# Board.net
KiCad netlist of a schematic drawn in EAGLE
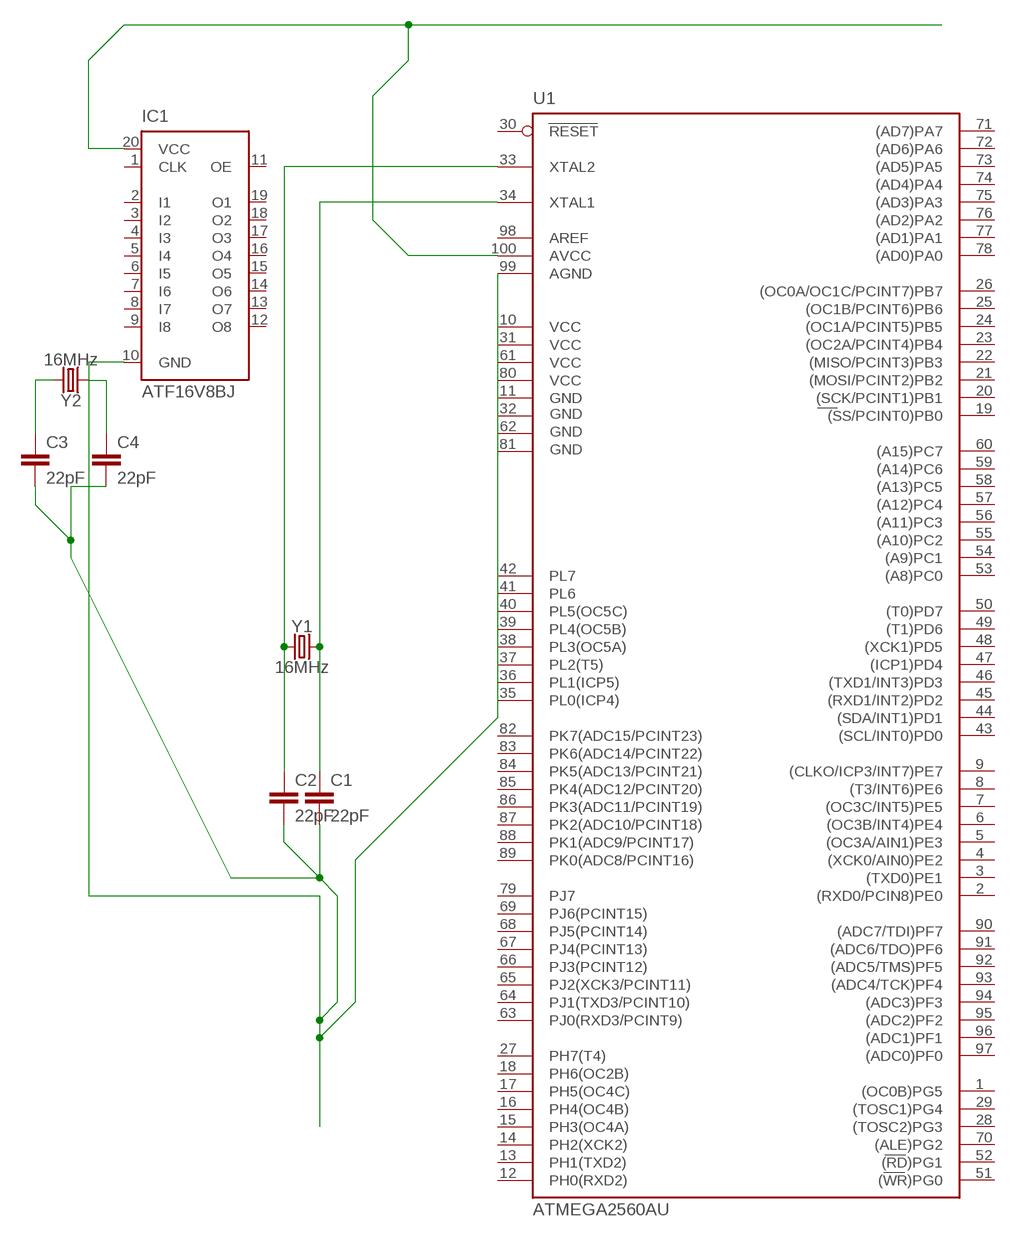
[diagram p0: schematic, sheet 1]

(export (version "E")
  (design (tool "Eeschema 10.0.6"))
  (components
    (comp (ref "C1")
      (value "22pF")
      (footprint "eagle-import:0603")
      (libsource (lib "eagle-import") (part "22PF-0603-50V-5%"))
    )
    (comp (ref "C2")
      (value "22pF")
      (footprint "eagle-import:0603")
      (libsource (lib "eagle-import") (part "22PF-0603-50V-5%"))
    )
    (comp (ref "C3")
      (value "22pF")
      (footprint "eagle-import:0603")
      (libsource (lib "eagle-import") (part "22PF-0603-50V-5%"))
    )
    (comp (ref "C4")
      (value "22pF")
      (footprint "eagle-import:0603")
      (libsource (lib "eagle-import") (part "22PF-0603-50V-5%"))
    )
    (comp (ref "IC1")
      (value "ATF16V8BJ")
      (footprint "eagle-import:PLCC20")
      (fields (field (name "MPN") "ATF16V8CZ-15JU"))
      (libsource (lib "eagle-import") (part "ATF16V8BJ"))
    )
    (comp (ref "U1")
      (value "ATMEGA2560AU")
      (footprint "eagle-import:TQFP100")
      (libsource (lib "eagle-import") (part "ATMEGA2560AU"))
    )
    (comp (ref "Y1")
      (value "16MHz")
      (footprint "eagle-import:CRYSTAL-SMD-5X3.2-4PAD")
      (libsource (lib "eagle-import") (part "CRYSTAL-16MHZSMD-5X3.2"))
    )
    (comp (ref "Y2")
      (value "16MHz")
      (footprint "eagle-import:CRYSTAL-SMD-5X3.2-4PAD")
      (libsource (lib "eagle-import") (part "CRYSTAL-16MHZSMD-5X3.2"))
    )
  )
  (nets
    (net (code "1") (name "/GND") (class "Default")
      (node (ref "U1") (pin "11") (pinfunction "GND_11") (pintype "power_in"))
    )
    (net (code "2") (name "/GND1") (class "Default")
      (node (ref "U1") (pin "32") (pinfunction "GND1_32") (pintype "power_in"))
    )
    (net (code "3") (name "/GND2") (class "Default")
      (node (ref "U1") (pin "62") (pinfunction "GND2_62") (pintype "power_in"))
    )
    (net (code "4") (name "/GND3") (class "Default")
      (node (ref "U1") (pin "81") (pinfunction "GND3_81") (pintype "power_in"))
    )
    (net (code "5") (name "/VCC") (class "Default")
      (node (ref "U1") (pin "10") (pinfunction "VCC_10") (pintype "power_in"))
    )
    (net (code "6") (name "/VCC1") (class "Default")
      (node (ref "U1") (pin "31") (pinfunction "VCC1_31") (pintype "power_in"))
    )
    (net (code "7") (name "/VCC2") (class "Default")
      (node (ref "U1") (pin "61") (pinfunction "VCC2_61") (pintype "power_in"))
    )
    (net (code "8") (name "/VCC3") (class "Default")
      (node (ref "U1") (pin "80") (pinfunction "VCC3_80") (pintype "power_in"))
    )
    (net (code "9") (name "Net-(C4-Pad1)") (class "Default")
      (node (ref "C4") (pin "1") (pinfunction "1_1") (pintype "passive"))
      (node (ref "Y2") (pin "1") (pinfunction "1_1") (pintype "passive"))
    )
    (net (code "10") (name "Net-(IC1-GND)") (class "Default")
      (node (ref "C1") (pin "2") (pinfunction "2_2") (pintype "passive"))
      (node (ref "C2") (pin "2") (pinfunction "2_2") (pintype "passive"))
      (node (ref "C3") (pin "2") (pinfunction "2_2") (pintype "passive"))
      (node (ref "C4") (pin "2") (pinfunction "2_2") (pintype "passive"))
      (node (ref "IC1") (pin "10") (pinfunction "GND_10") (pintype "power_in"))
      (node (ref "U1") (pin "99") (pinfunction "AGND_99") (pintype "power_in"))
    )
    (net (code "11") (name "Net-(IC1-VCC)") (class "Default")
      (node (ref "IC1") (pin "20") (pinfunction "VCC_20") (pintype "power_in"))
      (node (ref "U1") (pin "100") (pinfunction "AVCC_100") (pintype "power_in"))
    )
    (net (code "12") (name "Net-(U1-XTAL1)") (class "Default")
      (node (ref "C1") (pin "1") (pinfunction "1_1") (pintype "passive"))
      (node (ref "U1") (pin "34") (pinfunction "XTAL1_34") (pintype "input"))
      (node (ref "Y1") (pin "3") (pinfunction "2_3") (pintype "passive"))
    )
    (net (code "13") (name "Net-(U1-XTAL2)") (class "Default")
      (node (ref "C2") (pin "1") (pinfunction "1_1") (pintype "passive"))
      (node (ref "U1") (pin "33") (pinfunction "XTAL2_33") (pintype "output"))
      (node (ref "Y1") (pin "1") (pinfunction "1_1") (pintype "passive"))
    )
    (net (code "14") (name "Net-(Y2-2)") (class "Default")
      (node (ref "C3") (pin "1") (pinfunction "1_1") (pintype "passive"))
      (node (ref "Y2") (pin "3") (pinfunction "2_3") (pintype "passive"))
    )
    (net (code "15") (name "unconnected-(IC1-CLK-Pad1)") (class "Default")
      (node (ref "IC1") (pin "1") (pinfunction "CLK_1") (pintype "input"))
    )
    (net (code "16") (name "unconnected-(IC1-I1-Pad2)") (class "Default")
      (node (ref "IC1") (pin "2") (pinfunction "I1_2") (pintype "input"))
    )
    (net (code "17") (name "unconnected-(IC1-I2-Pad3)") (class "Default")
      (node (ref "IC1") (pin "3") (pinfunction "I2_3") (pintype "input"))
    )
    (net (code "18") (name "unconnected-(IC1-I3-Pad4)") (class "Default")
      (node (ref "IC1") (pin "4") (pinfunction "I3_4") (pintype "input"))
    )
    (net (code "19") (name "unconnected-(IC1-I4-Pad5)") (class "Default")
      (node (ref "IC1") (pin "5") (pinfunction "I4_5") (pintype "input"))
    )
    (net (code "20") (name "unconnected-(IC1-I5-Pad6)") (class "Default")
      (node (ref "IC1") (pin "6") (pinfunction "I5_6") (pintype "input"))
    )
    (net (code "21") (name "unconnected-(IC1-I6-Pad7)") (class "Default")
      (node (ref "IC1") (pin "7") (pinfunction "I6_7") (pintype "input"))
    )
    (net (code "22") (name "unconnected-(IC1-I7-Pad8)") (class "Default")
      (node (ref "IC1") (pin "8") (pinfunction "I7_8") (pintype "input"))
    )
    (net (code "23") (name "unconnected-(IC1-I8-Pad9)") (class "Default")
      (node (ref "IC1") (pin "9") (pinfunction "I8_9") (pintype "input"))
    )
    (net (code "24") (name "unconnected-(IC1-O1-Pad19)") (class "Default")
      (node (ref "IC1") (pin "19") (pinfunction "O1_19") (pintype "output"))
    )
    (net (code "25") (name "unconnected-(IC1-O2-Pad18)") (class "Default")
      (node (ref "IC1") (pin "18") (pinfunction "O2_18") (pintype "output"))
    )
    (net (code "26") (name "unconnected-(IC1-O3-Pad17)") (class "Default")
      (node (ref "IC1") (pin "17") (pinfunction "O3_17") (pintype "output"))
    )
    (net (code "27") (name "unconnected-(IC1-O4-Pad16)") (class "Default")
      (node (ref "IC1") (pin "16") (pinfunction "O4_16") (pintype "output"))
    )
    (net (code "28") (name "unconnected-(IC1-O5-Pad15)") (class "Default")
      (node (ref "IC1") (pin "15") (pinfunction "O5_15") (pintype "output"))
    )
    (net (code "29") (name "unconnected-(IC1-O6-Pad14)") (class "Default")
      (node (ref "IC1") (pin "14") (pinfunction "O6_14") (pintype "output"))
    )
    (net (code "30") (name "unconnected-(IC1-O7-Pad13)") (class "Default")
      (node (ref "IC1") (pin "13") (pinfunction "O7_13") (pintype "output"))
    )
    (net (code "31") (name "unconnected-(IC1-O8-Pad12)") (class "Default")
      (node (ref "IC1") (pin "12") (pinfunction "O8_12") (pintype "output"))
    )
    (net (code "32") (name "unconnected-(IC1-OE-Pad11)") (class "Default")
      (node (ref "IC1") (pin "11") (pinfunction "OE_11") (pintype "input"))
    )
    (net (code "33") (name "unconnected-(U1-(A8)PC0-Pad53)") (class "Default")
      (node (ref "U1") (pin "53") (pinfunction "(A8)PC0_53") (pintype "bidirectional"))
    )
    (net (code "34") (name "unconnected-(U1-(A9)PC1-Pad54)") (class "Default")
      (node (ref "U1") (pin "54") (pinfunction "(A9)PC1_54") (pintype "bidirectional"))
    )
    (net (code "35") (name "unconnected-(U1-(A10)PC2-Pad55)") (class "Default")
      (node (ref "U1") (pin "55") (pinfunction "(A10)PC2_55") (pintype "bidirectional"))
    )
    (net (code "36") (name "unconnected-(U1-(A11)PC3-Pad56)") (class "Default")
      (node (ref "U1") (pin "56") (pinfunction "(A11)PC3_56") (pintype "bidirectional"))
    )
    (net (code "37") (name "unconnected-(U1-(A12)PC4-Pad57)") (class "Default")
      (node (ref "U1") (pin "57") (pinfunction "(A12)PC4_57") (pintype "bidirectional"))
    )
    (net (code "38") (name "unconnected-(U1-(A13)PC5-Pad58)") (class "Default")
      (node (ref "U1") (pin "58") (pinfunction "(A13)PC5_58") (pintype "bidirectional"))
    )
    (net (code "39") (name "unconnected-(U1-(A14)PC6-Pad59)") (class "Default")
      (node (ref "U1") (pin "59") (pinfunction "(A14)PC6_59") (pintype "bidirectional"))
    )
    (net (code "40") (name "unconnected-(U1-(A15)PC7-Pad60)") (class "Default")
      (node (ref "U1") (pin "60") (pinfunction "(A15)PC7_60") (pintype "bidirectional"))
    )
    (net (code "41") (name "unconnected-(U1-(AD0)PA0-Pad78)") (class "Default")
      (node (ref "U1") (pin "78") (pinfunction "(AD0)PA0_78") (pintype "bidirectional"))
    )
    (net (code "42") (name "unconnected-(U1-(AD1)PA1-Pad77)") (class "Default")
      (node (ref "U1") (pin "77") (pinfunction "(AD1)PA1_77") (pintype "bidirectional"))
    )
    (net (code "43") (name "unconnected-(U1-(AD2)PA2-Pad76)") (class "Default")
      (node (ref "U1") (pin "76") (pinfunction "(AD2)PA2_76") (pintype "bidirectional"))
    )
    (net (code "44") (name "unconnected-(U1-(AD3)PA3-Pad75)") (class "Default")
      (node (ref "U1") (pin "75") (pinfunction "(AD3)PA3_75") (pintype "bidirectional"))
    )
    (net (code "45") (name "unconnected-(U1-(AD4)PA4-Pad74)") (class "Default")
      (node (ref "U1") (pin "74") (pinfunction "(AD4)PA4_74") (pintype "bidirectional"))
    )
    (net (code "46") (name "unconnected-(U1-(AD5)PA5-Pad73)") (class "Default")
      (node (ref "U1") (pin "73") (pinfunction "(AD5)PA5_73") (pintype "bidirectional"))
    )
    (net (code "47") (name "unconnected-(U1-(AD6)PA6-Pad72)") (class "Default")
      (node (ref "U1") (pin "72") (pinfunction "(AD6)PA6_72") (pintype "bidirectional"))
    )
    (net (code "48") (name "unconnected-(U1-(AD7)PA7-Pad71)") (class "Default")
      (node (ref "U1") (pin "71") (pinfunction "(AD7)PA7_71") (pintype "bidirectional"))
    )
    (net (code "49") (name "unconnected-(U1-(ADC0)PF0-Pad97)") (class "Default")
      (node (ref "U1") (pin "97") (pinfunction "(ADC0)PF0_97") (pintype "bidirectional"))
    )
    (net (code "50") (name "unconnected-(U1-(ADC1)PF1-Pad96)") (class "Default")
      (node (ref "U1") (pin "96") (pinfunction "(ADC1)PF1_96") (pintype "bidirectional"))
    )
    (net (code "51") (name "unconnected-(U1-(ADC2)PF2-Pad95)") (class "Default")
      (node (ref "U1") (pin "95") (pinfunction "(ADC2)PF2_95") (pintype "bidirectional"))
    )
    (net (code "52") (name "unconnected-(U1-(ADC3)PF3-Pad94)") (class "Default")
      (node (ref "U1") (pin "94") (pinfunction "(ADC3)PF3_94") (pintype "bidirectional"))
    )
    (net (code "53") (name "unconnected-(U1-(ADC4{slash}TCK)PF4-Pad93)") (class "Default")
      (node (ref "U1") (pin "93") (pinfunction "(ADC4/TCK)PF4_93") (pintype "bidirectional"))
    )
    (net (code "54") (name "unconnected-(U1-(ADC5{slash}TMS)PF5-Pad92)") (class "Default")
      (node (ref "U1") (pin "92") (pinfunction "(ADC5/TMS)PF5_92") (pintype "bidirectional"))
    )
    (net (code "55") (name "unconnected-(U1-(ADC6{slash}TDO)PF6-Pad91)") (class "Default")
      (node (ref "U1") (pin "91") (pinfunction "(ADC6/TDO)PF6_91") (pintype "bidirectional"))
    )
    (net (code "56") (name "unconnected-(U1-(ADC7{slash}TDI)PF7-Pad90)") (class "Default")
      (node (ref "U1") (pin "90") (pinfunction "(ADC7/TDI)PF7_90") (pintype "bidirectional"))
    )
    (net (code "57") (name "unconnected-(U1-(ALE)PG2-Pad70)") (class "Default")
      (node (ref "U1") (pin "70") (pinfunction "(ALE)PG2_70") (pintype "bidirectional"))
    )
    (net (code "58") (name "unconnected-(U1-(CLKO{slash}ICP3{slash}INT7)PE7-Pad9)") (class "Default")
      (node (ref "U1") (pin "9") (pinfunction "(CLKO/ICP3/INT7)PE7_9") (pintype "bidirectional"))
    )
    (net (code "59") (name "unconnected-(U1-(ICP1)PD4-Pad47)") (class "Default")
      (node (ref "U1") (pin "47") (pinfunction "(ICP1)PD4_47") (pintype "bidirectional"))
    )
    (net (code "60") (name "unconnected-(U1-(MISO{slash}PCINT3)PB3-Pad22)") (class "Default")
      (node (ref "U1") (pin "22") (pinfunction "(MISO/PCINT3)PB3_22") (pintype "bidirectional"))
    )
    (net (code "61") (name "unconnected-(U1-(MOSI{slash}PCINT2)PB2-Pad21)") (class "Default")
      (node (ref "U1") (pin "21") (pinfunction "(MOSI/PCINT2)PB2_21") (pintype "bidirectional"))
    )
    (net (code "62") (name "unconnected-(U1-(OC0A{slash}OC1C{slash}PCINT7)PB7-Pad26)") (class "Default")
      (node (ref "U1") (pin "26") (pinfunction "(OC0A/OC1C/PCINT7)PB7_26") (pintype "bidirectional"))
    )
    (net (code "63") (name "unconnected-(U1-(OC0B)PG5-Pad1)") (class "Default")
      (node (ref "U1") (pin "1") (pinfunction "(OC0B)PG5_1") (pintype "bidirectional"))
    )
    (net (code "64") (name "unconnected-(U1-(OC1A{slash}PCINT5)PB5-Pad24)") (class "Default")
      (node (ref "U1") (pin "24") (pinfunction "(OC1A/PCINT5)PB5_24") (pintype "bidirectional"))
    )
    (net (code "65") (name "unconnected-(U1-(OC1B{slash}PCINT6)PB6-Pad25)") (class "Default")
      (node (ref "U1") (pin "25") (pinfunction "(OC1B/PCINT6)PB6_25") (pintype "bidirectional"))
    )
    (net (code "66") (name "unconnected-(U1-(OC2A{slash}PCINT4)PB4-Pad23)") (class "Default")
      (node (ref "U1") (pin "23") (pinfunction "(OC2A/PCINT4)PB4_23") (pintype "bidirectional"))
    )
    (net (code "67") (name "unconnected-(U1-(OC3A{slash}AIN1)PE3-Pad5)") (class "Default")
      (node (ref "U1") (pin "5") (pinfunction "(OC3A/AIN1)PE3_5") (pintype "bidirectional"))
    )
    (net (code "68") (name "unconnected-(U1-(OC3B{slash}INT4)PE4-Pad6)") (class "Default")
      (node (ref "U1") (pin "6") (pinfunction "(OC3B/INT4)PE4_6") (pintype "bidirectional"))
    )
    (net (code "69") (name "unconnected-(U1-(OC3C{slash}INT5)PE5-Pad7)") (class "Default")
      (node (ref "U1") (pin "7") (pinfunction "(OC3C/INT5)PE5_7") (pintype "bidirectional"))
    )
    (net (code "70") (name "unconnected-(U1-(RD)PG1-Pad52)") (class "Default")
      (node (ref "U1") (pin "52") (pinfunction "(RD)PG1_52") (pintype "bidirectional"))
    )
    (net (code "71") (name "unconnected-(U1-(RXD0{slash}PCIN8)PE0-Pad2)") (class "Default")
      (node (ref "U1") (pin "2") (pinfunction "(RXD0/PCIN8)PE0_2") (pintype "bidirectional"))
    )
    (net (code "72") (name "unconnected-(U1-(RXD1{slash}INT2)PD2-Pad45)") (class "Default")
      (node (ref "U1") (pin "45") (pinfunction "(RXD1/INT2)PD2_45") (pintype "bidirectional"))
    )
    (net (code "73") (name "unconnected-(U1-(SCK{slash}PCINT1)PB1-Pad20)") (class "Default")
      (node (ref "U1") (pin "20") (pinfunction "(SCK/PCINT1)PB1_20") (pintype "bidirectional"))
    )
    (net (code "74") (name "unconnected-(U1-(SCL{slash}INT0)PD0-Pad43)") (class "Default")
      (node (ref "U1") (pin "43") (pinfunction "(SCL/INT0)PD0_43") (pintype "bidirectional"))
    )
    (net (code "75") (name "unconnected-(U1-(SDA{slash}INT1)PD1-Pad44)") (class "Default")
      (node (ref "U1") (pin "44") (pinfunction "(SDA/INT1)PD1_44") (pintype "bidirectional"))
    )
    (net (code "76") (name "unconnected-(U1-(SS{slash}PCINT0)PB0-Pad19)") (class "Default")
      (node (ref "U1") (pin "19") (pinfunction "(SS/PCINT0)PB0_19") (pintype "bidirectional"))
    )
    (net (code "77") (name "unconnected-(U1-(T0)PD7-Pad50)") (class "Default")
      (node (ref "U1") (pin "50") (pinfunction "(T0)PD7_50") (pintype "bidirectional"))
    )
    (net (code "78") (name "unconnected-(U1-(T1)PD6-Pad49)") (class "Default")
      (node (ref "U1") (pin "49") (pinfunction "(T1)PD6_49") (pintype "bidirectional"))
    )
    (net (code "79") (name "unconnected-(U1-(T3{slash}INT6)PE6-Pad8)") (class "Default")
      (node (ref "U1") (pin "8") (pinfunction "(T3/INT6)PE6_8") (pintype "bidirectional"))
    )
    (net (code "80") (name "unconnected-(U1-(TOSC1)PG4-Pad29)") (class "Default")
      (node (ref "U1") (pin "29") (pinfunction "(TOSC1)PG4_29") (pintype "bidirectional"))
    )
    (net (code "81") (name "unconnected-(U1-(TOSC2)PG3-Pad28)") (class "Default")
      (node (ref "U1") (pin "28") (pinfunction "(TOSC2)PG3_28") (pintype "bidirectional"))
    )
    (net (code "82") (name "unconnected-(U1-(TXD0)PE1-Pad3)") (class "Default")
      (node (ref "U1") (pin "3") (pinfunction "(TXD0)PE1_3") (pintype "bidirectional"))
    )
    (net (code "83") (name "unconnected-(U1-(TXD1{slash}INT3)PD3-Pad46)") (class "Default")
      (node (ref "U1") (pin "46") (pinfunction "(TXD1/INT3)PD3_46") (pintype "bidirectional"))
    )
    (net (code "84") (name "unconnected-(U1-(WR)PG0-Pad51)") (class "Default")
      (node (ref "U1") (pin "51") (pinfunction "(WR)PG0_51") (pintype "bidirectional"))
    )
    (net (code "85") (name "unconnected-(U1-(XCK0{slash}AIN0)PE2-Pad4)") (class "Default")
      (node (ref "U1") (pin "4") (pinfunction "(XCK0/AIN0)PE2_4") (pintype "bidirectional"))
    )
    (net (code "86") (name "unconnected-(U1-(XCK1)PD5-Pad48)") (class "Default")
      (node (ref "U1") (pin "48") (pinfunction "(XCK1)PD5_48") (pintype "bidirectional"))
    )
    (net (code "87") (name "unconnected-(U1-AREF-Pad98)") (class "Default")
      (node (ref "U1") (pin "98") (pinfunction "AREF_98") (pintype "bidirectional"))
    )
    (net (code "88") (name "unconnected-(U1-PH0(RXD2)-Pad12)") (class "Default")
      (node (ref "U1") (pin "12") (pinfunction "PH0(RXD2)_12") (pintype "bidirectional"))
    )
    (net (code "89") (name "unconnected-(U1-PH1(TXD2)-Pad13)") (class "Default")
      (node (ref "U1") (pin "13") (pinfunction "PH1(TXD2)_13") (pintype "bidirectional"))
    )
    (net (code "90") (name "unconnected-(U1-PH2(XCK2)-Pad14)") (class "Default")
      (node (ref "U1") (pin "14") (pinfunction "PH2(XCK2)_14") (pintype "bidirectional"))
    )
    (net (code "91") (name "unconnected-(U1-PH3(OC4A)-Pad15)") (class "Default")
      (node (ref "U1") (pin "15") (pinfunction "PH3(OC4A)_15") (pintype "bidirectional"))
    )
    (net (code "92") (name "unconnected-(U1-PH4(OC4B)-Pad16)") (class "Default")
      (node (ref "U1") (pin "16") (pinfunction "PH4(OC4B)_16") (pintype "bidirectional"))
    )
    (net (code "93") (name "unconnected-(U1-PH5(OC4C)-Pad17)") (class "Default")
      (node (ref "U1") (pin "17") (pinfunction "PH5(OC4C)_17") (pintype "bidirectional"))
    )
    (net (code "94") (name "unconnected-(U1-PH6(OC2B)-Pad18)") (class "Default")
      (node (ref "U1") (pin "18") (pinfunction "PH6(OC2B)_18") (pintype "bidirectional"))
    )
    (net (code "95") (name "unconnected-(U1-PH7(T4)-Pad27)") (class "Default")
      (node (ref "U1") (pin "27") (pinfunction "PH7(T4)_27") (pintype "bidirectional"))
    )
    (net (code "96") (name "unconnected-(U1-PJ0(RXD3{slash}PCINT9)-Pad63)") (class "Default")
      (node (ref "U1") (pin "63") (pinfunction "PJ0(RXD3/PCINT9)_63") (pintype "bidirectional"))
    )
    (net (code "97") (name "unconnected-(U1-PJ1(TXD3{slash}PCINT10)-Pad64)") (class "Default")
      (node (ref "U1") (pin "64") (pinfunction "PJ1(TXD3/PCINT10)_64") (pintype "bidirectional"))
    )
    (net (code "98") (name "unconnected-(U1-PJ2(XCK3{slash}PCINT11)-Pad65)") (class "Default")
      (node (ref "U1") (pin "65") (pinfunction "PJ2(XCK3/PCINT11)_65") (pintype "bidirectional"))
    )
    (net (code "99") (name "unconnected-(U1-PJ3(PCINT12)-Pad66)") (class "Default")
      (node (ref "U1") (pin "66") (pinfunction "PJ3(PCINT12)_66") (pintype "bidirectional"))
    )
    (net (code "100") (name "unconnected-(U1-PJ4(PCINT13)-Pad67)") (class "Default")
      (node (ref "U1") (pin "67") (pinfunction "PJ4(PCINT13)_67") (pintype "bidirectional"))
    )
    (net (code "101") (name "unconnected-(U1-PJ5(PCINT14)-Pad68)") (class "Default")
      (node (ref "U1") (pin "68") (pinfunction "PJ5(PCINT14)_68") (pintype "bidirectional"))
    )
    (net (code "102") (name "unconnected-(U1-PJ6(PCINT15)-Pad69)") (class "Default")
      (node (ref "U1") (pin "69") (pinfunction "PJ6(PCINT15)_69") (pintype "bidirectional"))
    )
    (net (code "103") (name "unconnected-(U1-PJ7-Pad79)") (class "Default")
      (node (ref "U1") (pin "79") (pinfunction "PJ7_79") (pintype "bidirectional"))
    )
    (net (code "104") (name "unconnected-(U1-PK0(ADC8{slash}PCINT16)-Pad89)") (class "Default")
      (node (ref "U1") (pin "89") (pinfunction "PK0(ADC8/PCINT16)_89") (pintype "bidirectional"))
    )
    (net (code "105") (name "unconnected-(U1-PK1(ADC9{slash}PCINT17)-Pad88)") (class "Default")
      (node (ref "U1") (pin "88") (pinfunction "PK1(ADC9/PCINT17)_88") (pintype "bidirectional"))
    )
    (net (code "106") (name "unconnected-(U1-PK2(ADC10{slash}PCINT18)-Pad87)") (class "Default")
      (node (ref "U1") (pin "87") (pinfunction "PK2(ADC10/PCINT18)_87") (pintype "bidirectional"))
    )
    (net (code "107") (name "unconnected-(U1-PK3(ADC11{slash}PCINT19)-Pad86)") (class "Default")
      (node (ref "U1") (pin "86") (pinfunction "PK3(ADC11/PCINT19)_86") (pintype "bidirectional"))
    )
    (net (code "108") (name "unconnected-(U1-PK4(ADC12{slash}PCINT20)-Pad85)") (class "Default")
      (node (ref "U1") (pin "85") (pinfunction "PK4(ADC12/PCINT20)_85") (pintype "bidirectional"))
    )
    (net (code "109") (name "unconnected-(U1-PK5(ADC13{slash}PCINT21)-Pad84)") (class "Default")
      (node (ref "U1") (pin "84") (pinfunction "PK5(ADC13/PCINT21)_84") (pintype "bidirectional"))
    )
    (net (code "110") (name "unconnected-(U1-PK6(ADC14{slash}PCINT22)-Pad83)") (class "Default")
      (node (ref "U1") (pin "83") (pinfunction "PK6(ADC14/PCINT22)_83") (pintype "bidirectional"))
    )
    (net (code "111") (name "unconnected-(U1-PK7(ADC15{slash}PCINT23)-Pad82)") (class "Default")
      (node (ref "U1") (pin "82") (pinfunction "PK7(ADC15/PCINT23)_82") (pintype "bidirectional"))
    )
    (net (code "112") (name "unconnected-(U1-PL0(ICP4)-Pad35)") (class "Default")
      (node (ref "U1") (pin "35") (pinfunction "PL0(ICP4)_35") (pintype "bidirectional"))
    )
    (net (code "113") (name "unconnected-(U1-PL1(ICP5)-Pad36)") (class "Default")
      (node (ref "U1") (pin "36") (pinfunction "PL1(ICP5)_36") (pintype "bidirectional"))
    )
    (net (code "114") (name "unconnected-(U1-PL2(T5)-Pad37)") (class "Default")
      (node (ref "U1") (pin "37") (pinfunction "PL2(T5)_37") (pintype "bidirectional"))
    )
    (net (code "115") (name "unconnected-(U1-PL3(OC5A)-Pad38)") (class "Default")
      (node (ref "U1") (pin "38") (pinfunction "PL3(OC5A)_38") (pintype "bidirectional"))
    )
    (net (code "116") (name "unconnected-(U1-PL4(OC5B)-Pad39)") (class "Default")
      (node (ref "U1") (pin "39") (pinfunction "PL4(OC5B)_39") (pintype "bidirectional"))
    )
    (net (code "117") (name "unconnected-(U1-PL5(OC5C)-Pad40)") (class "Default")
      (node (ref "U1") (pin "40") (pinfunction "PL5(OC5C)_40") (pintype "bidirectional"))
    )
    (net (code "118") (name "unconnected-(U1-PL6-Pad41)") (class "Default")
      (node (ref "U1") (pin "41") (pinfunction "PL6_41") (pintype "bidirectional"))
    )
    (net (code "119") (name "unconnected-(U1-PL7-Pad42)") (class "Default")
      (node (ref "U1") (pin "42") (pinfunction "PL7_42") (pintype "bidirectional"))
    )
    (net (code "120") (name "unconnected-(U1-RESET-Pad30)") (class "Default")
      (node (ref "U1") (pin "30") (pinfunction "RESET_30") (pintype "input"))
    )
  )
)
